# ArduinoUno.net
KiCad netlist of a schematic drawn in Altium Designer
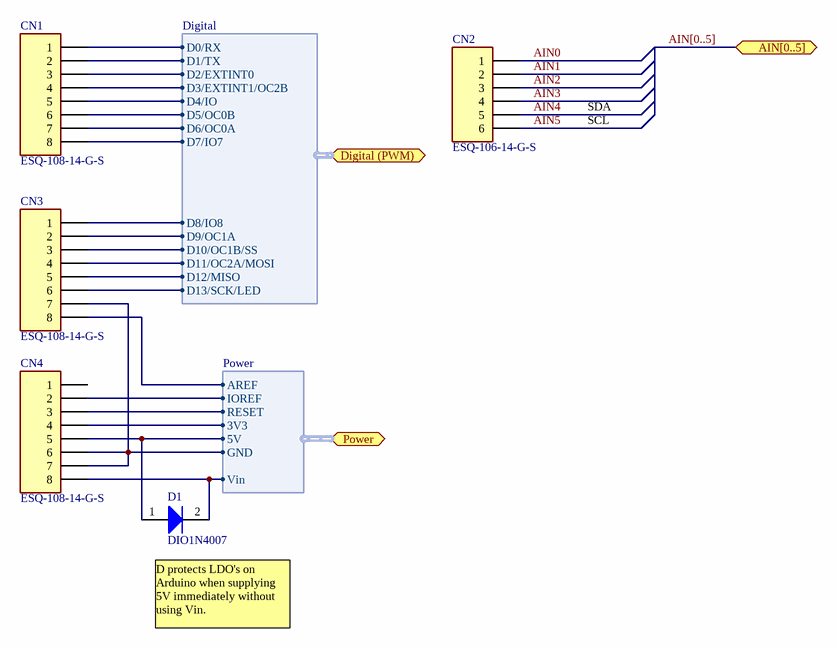
[diagram p0: ArduinoUno.SchDoc]

(export (version "E")
  (design (tool "Eeschema 10.0.6"))
  (components
    (comp (ref "CN1")
      (value "ESQ-108-14-G-S")
      (footprint "CN_SAMTEC_ESQ-108-14-G-S")
      (fields (field (name "MANUFACTURER") "Samtec"))
      (libsource (lib "Testing") (part "CN_8P"))
    )
    (comp (ref "CN2")
      (value "ESQ-106-14-G-S")
      (footprint "CN_SAMTEC_ESQ-106-14-G-S")
      (fields (field (name "MANUFACTURER") "Samtec"))
      (libsource (lib "Testing") (part "CN_6P"))
    )
    (comp (ref "CN3")
      (value "ESQ-108-14-G-S")
      (footprint "CN_SAMTEC_ESQ-108-14-G-S")
      (fields (field (name "MANUFACTURER") "Samtec"))
      (libsource (lib "Testing") (part "CN_8P"))
    )
    (comp (ref "CN4")
      (value "ESQ-108-14-G-S")
      (footprint "CN_SAMTEC_ESQ-108-14-G-S")
      (fields (field (name "MANUFACTURER") "Samtec"))
      (libsource (lib "Testing") (part "CN_8P"))
    )
    (comp (ref "D1")
      (value "DIO1N4007")
      (footprint "DI_DO-41")
      (description "1 Amp General Purpose Rectifier")
      (libsource (lib "Testing") (part "DI_DIODE"))
    )
  )
  (nets
    (net (code "3") (name "/3V3") (class "Default")
      (node (ref "CN4") (pin "4") (pinfunction "4_4") (pintype "passive"))
    )
    (net (code "4") (name "/5V") (class "Default")
      (node (ref "CN4") (pin "5") (pinfunction "5_5") (pintype "passive"))
      (node (ref "D1") (pin "1") (pinfunction "A_1") (pintype "passive"))
    )
    (net (code "5") (name "/AIN0") (class "Default")
      (node (ref "CN2") (pin "1") (pinfunction "1_1") (pintype "passive"))
    )
    (net (code "6") (name "/AIN1") (class "Default")
      (node (ref "CN2") (pin "2") (pinfunction "2_2") (pintype "passive"))
    )
    (net (code "7") (name "/AIN2") (class "Default")
      (node (ref "CN2") (pin "3") (pinfunction "3_3") (pintype "passive"))
    )
    (net (code "8") (name "/AIN3") (class "Default")
      (node (ref "CN2") (pin "4") (pinfunction "4_4") (pintype "passive"))
    )
    (net (code "9") (name "/AIN4") (class "Default")
      (node (ref "CN2") (pin "5") (pinfunction "5_5") (pintype "passive"))
    )
    (net (code "10") (name "/AIN5") (class "Default")
      (node (ref "CN2") (pin "6") (pinfunction "6_6") (pintype "passive"))
    )
    (net (code "12") (name "/AREF") (class "Default")
      (node (ref "CN3") (pin "8") (pinfunction "8_8") (pintype "passive"))
    )
    (net (code "13") (name "/D0{slash}RX") (class "Default")
      (node (ref "CN1") (pin "1") (pinfunction "1_1") (pintype "passive"))
    )
    (net (code "14") (name "/D1{slash}TX") (class "Default")
      (node (ref "CN1") (pin "2") (pinfunction "2_2") (pintype "passive"))
    )
    (net (code "15") (name "/D2{slash}EXTINT0") (class "Default")
      (node (ref "CN1") (pin "3") (pinfunction "3_3") (pintype "passive"))
    )
    (net (code "16") (name "/D3{slash}EXTINT1{slash}OC2B") (class "Default")
      (node (ref "CN1") (pin "4") (pinfunction "4_4") (pintype "passive"))
    )
    (net (code "17") (name "/D4{slash}IO") (class "Default")
      (node (ref "CN1") (pin "5") (pinfunction "5_5") (pintype "passive"))
    )
    (net (code "18") (name "/D5{slash}OC0B") (class "Default")
      (node (ref "CN1") (pin "6") (pinfunction "6_6") (pintype "passive"))
    )
    (net (code "19") (name "/D6{slash}OC0A") (class "Default")
      (node (ref "CN1") (pin "7") (pinfunction "7_7") (pintype "passive"))
    )
    (net (code "20") (name "/D7{slash}IO7") (class "Default")
      (node (ref "CN1") (pin "8") (pinfunction "8_8") (pintype "passive"))
    )
    (net (code "21") (name "/D8{slash}IO8") (class "Default")
      (node (ref "CN3") (pin "1") (pinfunction "1_1") (pintype "passive"))
    )
    (net (code "22") (name "/D9{slash}OC1A") (class "Default")
      (node (ref "CN3") (pin "2") (pinfunction "2_2") (pintype "passive"))
    )
    (net (code "23") (name "/D10{slash}OC1B{slash}SS") (class "Default")
      (node (ref "CN3") (pin "3") (pinfunction "3_3") (pintype "passive"))
    )
    (net (code "24") (name "/D11{slash}OC2A{slash}MOSI") (class "Default")
      (node (ref "CN3") (pin "4") (pinfunction "4_4") (pintype "passive"))
    )
    (net (code "25") (name "/D12{slash}MISO") (class "Default")
      (node (ref "CN3") (pin "5") (pinfunction "5_5") (pintype "passive"))
    )
    (net (code "26") (name "/D13{slash}SCK{slash}LED") (class "Default")
      (node (ref "CN3") (pin "6") (pinfunction "6_6") (pintype "passive"))
    )
    (net (code "27") (name "/GND") (class "Default")
      (node (ref "CN3") (pin "7") (pinfunction "7_7") (pintype "passive"))
      (node (ref "CN4") (pin "6") (pinfunction "6_6") (pintype "passive"))
      (node (ref "CN4") (pin "7") (pinfunction "7_7") (pintype "passive"))
    )
    (net (code "28") (name "/IOREF") (class "Default")
      (node (ref "CN4") (pin "2") (pinfunction "2_2") (pintype "passive"))
    )
    (net (code "29") (name "/RESET") (class "Default")
      (node (ref "CN4") (pin "3") (pinfunction "3_3") (pintype "passive"))
    )
    (net (code "30") (name "/Vin") (class "Default")
      (node (ref "CN4") (pin "8") (pinfunction "8_8") (pintype "passive"))
      (node (ref "D1") (pin "2") (pinfunction "K_2") (pintype "passive"))
    )
    (net (code "33") (name "unconnected-(CN4-Pad1)") (class "Default")
      (node (ref "CN4") (pin "1") (pinfunction "1_1") (pintype "passive"))
    )
  )
)
